# CuC_ControlComm.net
KiCad netlist of a schematic drawn in Altium Designer
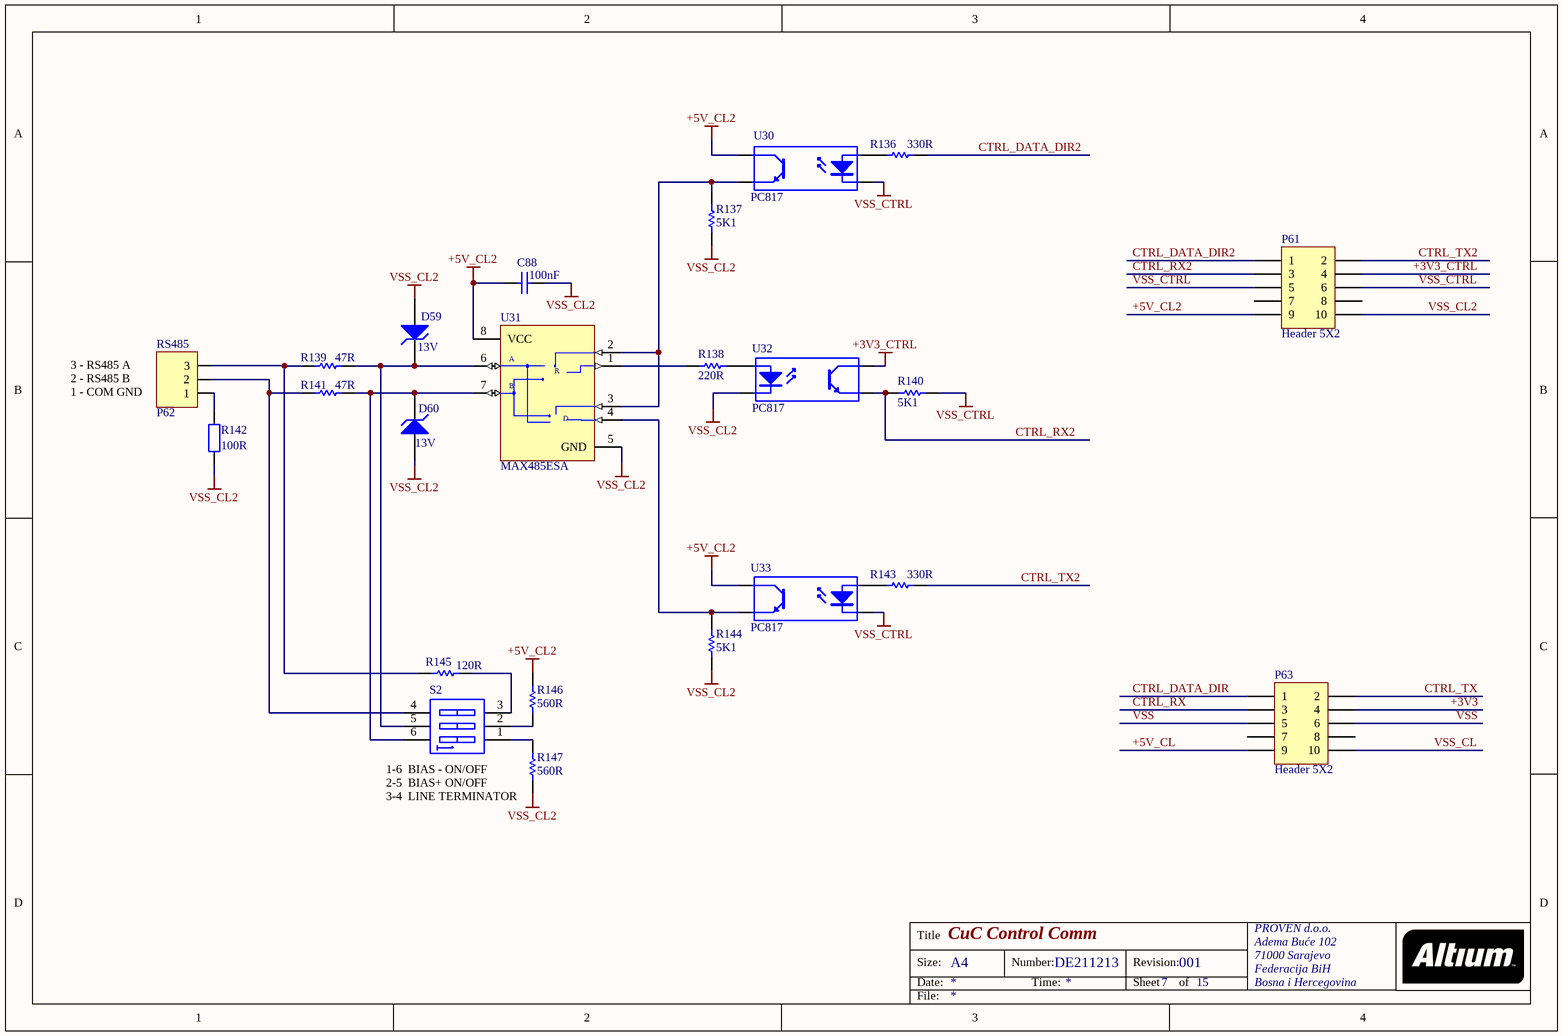
[diagram p0: CuC_ControlComm.SchDoc]

(export (version "E")
  (design (tool "Eeschema 10.0.6"))
  (components
    (comp (ref "C88")
      (value "100nF")
      (footprint "1206")
      (description "Ceramic Chip Capacitor - Standard")
      (fields (field (name "PUBLISHER") "Altium Limited"))
      (libsource (lib "KEMET Chip Capacitor") (part "C1206"))
    )
    (comp (ref "D59")
      (value "13V")
      (footprint "Miscellaneous Devices:DO-35A")
      (description "Zener Diode")
      (fields (field (name "PUBLISHER") "Altium Limited"))
      (libsource (lib "Miscellaneous Devices") (part "D Zener"))
    )
    (comp (ref "D60")
      (value "13V")
      (footprint "Miscellaneous Devices:DO-35A")
      (description "Zener Diode")
      (fields (field (name "PUBLISHER") "Altium Limited"))
      (libsource (lib "Miscellaneous Devices") (part "D Zener"))
    )
    (comp (ref "P61")
      (value "Header 5X2")
      (footprint "HDR2X5")
      (description "Header, 5-Pin, Dual row")
      (fields (field (name "PUBLISHER") "Altium Limited"))
      (libsource (lib "Miscellaneous Connectors") (part "Header 5X2"))
    )
    (comp (ref "P62")
      (value "RS485")
      (footprint "TERMINAL BLOK 3")
      (description "3 pinski terminal blok konektor")
      (libsource (lib "ProjectLibrary") (part "TERMINAL BLOK 3"))
    )
    (comp (ref "P63")
      (value "Header 5X2")
      (footprint "HDR2X5")
      (description "Header, 5-Pin, Dual row")
      (fields (field (name "PUBLISHER") "Altium Limited"))
      (libsource (lib "Miscellaneous Connectors") (part "Header 5X2"))
    )
    (comp (ref "R136")
      (value "330R")
      (footprint "ERA-0805")
      (fields (field (name "PUBLISHER") "Altium Limited"))
      (libsource (lib "Panasonic Resistor") (part "ERA6Y"))
    )
    (comp (ref "R137")
      (value "5K1")
      (footprint "8-1206")
      (description "Thick Film Chip Resistor, 1 Ohm to 10M Ohm Range, 5% Tolerance, 1206 Size, 0.25 W")
      (fields (field (name "PUBLISHER") "Altium Limited"))
      (libsource (lib "Panasonic Resistor") (part "ERJ8GE"))
    )
    (comp (ref "R138")
      (value "220R")
      (footprint "ERA-0805")
      (fields (field (name "PUBLISHER") "Altium Limited"))
      (libsource (lib "Panasonic Resistor") (part "ERAS"))
    )
    (comp (ref "R139")
      (value "47R")
      (footprint "ERA-0805")
      (fields (field (name "PUBLISHER") "Altium Limited"))
      (libsource (lib "Panasonic Resistor") (part "ERAS"))
    )
    (comp (ref "R140")
      (value "5K1")
      (footprint "8-1206")
      (description "Thick Film Chip Resistor, 1 Ohm to 10M Ohm Range, 5% Tolerance, 1206 Size, 0.25 W")
      (fields (field (name "PUBLISHER") "Altium Limited"))
      (libsource (lib "Panasonic Resistor") (part "ERJ8GE"))
    )
    (comp (ref "R141")
      (value "47R")
      (footprint "ERA-0805")
      (fields (field (name "PUBLISHER") "Altium Limited"))
      (libsource (lib "Panasonic Resistor") (part "ERAS"))
    )
    (comp (ref "R142")
      (value "100R")
      (footprint "AXIAL-0.4")
      (description "Resistor")
      (fields (field (name "PUBLISHER") "Altium Limited"))
      (libsource (lib "Miscellaneous Devices") (part "Res2"))
    )
    (comp (ref "R143")
      (value "330R")
      (footprint "ERA-0805")
      (fields (field (name "PUBLISHER") "Altium Limited"))
      (libsource (lib "Panasonic Resistor") (part "ERA6Y"))
    )
    (comp (ref "R144")
      (value "5K1")
      (footprint "8-1206")
      (description "Thick Film Chip Resistor, 1 Ohm to 10M Ohm Range, 5% Tolerance, 1206 Size, 0.25 W")
      (fields (field (name "PUBLISHER") "Altium Limited"))
      (libsource (lib "Panasonic Resistor") (part "ERJ8GE"))
    )
    (comp (ref "R145")
      (value "120R")
      (footprint "ERA-0805")
      (fields (field (name "PUBLISHER") "Altium Limited"))
      (libsource (lib "Panasonic Resistor") (part "ERAS"))
    )
    (comp (ref "R146")
      (value "560R")
      (footprint "ERA-0805")
      (fields (field (name "PUBLISHER") "Altium Limited"))
      (libsource (lib "Panasonic Resistor") (part "ERAS"))
    )
    (comp (ref "R147")
      (value "560R")
      (footprint "ERA-0805")
      (fields (field (name "PUBLISHER") "Altium Limited"))
      (libsource (lib "Panasonic Resistor") (part "ERAS"))
    )
    (comp (ref "S2")
      (value "~")
      (footprint "DIP-6")
      (description "DIP Switch, 3 Position, SPST")
      (fields (field (name "PUBLISHER") "Altium Limited"))
      (libsource (lib "Miscellaneous Devices") (part "SW DIP-3"))
    )
    (comp (ref "U30")
      (value "PC817")
      (footprint "DIP-4")
      (description "4-Pin Phototransistor Optocoupler")
      (fields (field (name "PUBLISHER") "Altium Limited"))
      (libsource (lib "Miscellaneous Devices") (part "Optoisolator1"))
    )
    (comp (ref "U31")
      (value "MAX485ESA")
      (footprint "NSO8_N")
      (description "Low-Power, Slew-Rate-Limited RS-485/RS-422 Transceiver")
      (fields (field (name "PUBLISHER") "Altium Limited"))
      (libsource (lib "Maxim Communication Transceiver") (part "MAX485ESA"))
    )
    (comp (ref "U32")
      (value "PC817")
      (footprint "DIP-4")
      (description "4-Pin Phototransistor Optocoupler")
      (fields (field (name "PUBLISHER") "Altium Limited"))
      (libsource (lib "Miscellaneous Devices") (part "Optoisolator1"))
    )
    (comp (ref "U33")
      (value "PC817")
      (footprint "DIP-4")
      (description "4-Pin Phototransistor Optocoupler")
      (fields (field (name "PUBLISHER") "Altium Limited"))
      (libsource (lib "Miscellaneous Devices") (part "Optoisolator1"))
    )
  )
  (nets
    (net (code "1") (name "+3V3_CTRL") (class "Default")
      (node (ref "P61") (pin "4") (pinfunction "4_4") (pintype "passive"))
      (node (ref "U32") (pin "4") (pinfunction "C_4") (pintype "passive"))
    )
    (net (code "2") (name "+5V_CL2") (class "Default")
      (node (ref "C88") (pin "2") (pinfunction "2_2") (pintype "passive"))
      (node (ref "P61") (pin "9") (pinfunction "9_9") (pintype "passive"))
      (node (ref "R146") (pin "2") (pinfunction "2_2") (pintype "passive"))
      (node (ref "U30") (pin "4") (pinfunction "C_4") (pintype "passive"))
      (node (ref "U31") (pin "8") (pinfunction "VCC_8") (pintype "power_in"))
      (node (ref "U33") (pin "4") (pinfunction "C_4") (pintype "passive"))
    )
    (net (code "3") (name "/+3V3") (class "Default")
      (node (ref "P63") (pin "4") (pinfunction "4_4") (pintype "passive"))
    )
    (net (code "4") (name "/+5V_CL") (class "Default")
      (node (ref "P63") (pin "9") (pinfunction "9_9") (pintype "passive"))
    )
    (net (code "5") (name "/CTRL_DATA_DIR") (class "Default")
      (node (ref "P63") (pin "1") (pinfunction "1_1") (pintype "passive"))
    )
    (net (code "6") (name "/CTRL_DATA_DIR2") (class "Default")
      (node (ref "P61") (pin "1") (pinfunction "1_1") (pintype "passive"))
      (node (ref "R136") (pin "2") (pinfunction "2_2") (pintype "passive"))
    )
    (net (code "7") (name "/CTRL_RX") (class "Default")
      (node (ref "P63") (pin "3") (pinfunction "3_3") (pintype "passive"))
    )
    (net (code "8") (name "/CTRL_RX2") (class "Default")
      (node (ref "P61") (pin "3") (pinfunction "3_3") (pintype "passive"))
      (node (ref "R140") (pin "1") (pinfunction "1_1") (pintype "passive"))
      (node (ref "U32") (pin "3") (pinfunction "E_3") (pintype "passive"))
    )
    (net (code "9") (name "/CTRL_TX") (class "Default")
      (node (ref "P63") (pin "2") (pinfunction "2_2") (pintype "passive"))
    )
    (net (code "10") (name "/CTRL_TX2") (class "Default")
      (node (ref "P61") (pin "2") (pinfunction "2_2") (pintype "passive"))
      (node (ref "R143") (pin "2") (pinfunction "2_2") (pintype "passive"))
    )
    (net (code "11") (name "/VSS") (class "Default")
      (node (ref "P63") (pin "5") (pinfunction "5_5") (pintype "passive"))
      (node (ref "P63") (pin "6") (pinfunction "6_6") (pintype "passive"))
    )
    (net (code "12") (name "/VSS_CL") (class "Default")
      (node (ref "P63") (pin "10") (pinfunction "10_10") (pintype "passive"))
    )
    (net (code "13") (name "Net-(D59-K)") (class "Default")
      (node (ref "D59") (pin "2") (pinfunction "K_2") (pintype "passive"))
      (node (ref "R139") (pin "2") (pinfunction "2_2") (pintype "passive"))
      (node (ref "S2") (pin "5") (pinfunction "B2_5") (pintype "passive"))
      (node (ref "U31") (pin "6") (pinfunction "A_6") (pintype "bidirectional"))
    )
    (net (code "14") (name "Net-(D60-K)") (class "Default")
      (node (ref "D60") (pin "2") (pinfunction "K_2") (pintype "passive"))
      (node (ref "R141") (pin "2") (pinfunction "2_2") (pintype "passive"))
      (node (ref "S2") (pin "6") (pinfunction "B1_6") (pintype "passive"))
      (node (ref "U31") (pin "7") (pinfunction "B_7") (pintype "bidirectional"))
    )
    (net (code "15") (name "Net-(P62-Pad1)") (class "Default")
      (node (ref "P62") (pin "1") (pinfunction "1_1") (pintype "passive"))
      (node (ref "R142") (pin "2") (pinfunction "2_2") (pintype "passive"))
    )
    (net (code "16") (name "Net-(P62-Pad3)") (class "Default")
      (node (ref "P62") (pin "3") (pinfunction "3_3") (pintype "passive"))
      (node (ref "R139") (pin "1") (pinfunction "1_1") (pintype "passive"))
      (node (ref "R145") (pin "1") (pinfunction "1_1") (pintype "passive"))
    )
    (net (code "17") (name "Net-(S2-A1)") (class "Default")
      (node (ref "R147") (pin "2") (pinfunction "2_2") (pintype "passive"))
      (node (ref "S2") (pin "1") (pinfunction "A1_1") (pintype "passive"))
    )
    (net (code "18") (name "Net-(S2-A2)") (class "Default")
      (node (ref "R146") (pin "1") (pinfunction "1_1") (pintype "passive"))
      (node (ref "S2") (pin "2") (pinfunction "A2_2") (pintype "passive"))
    )
    (net (code "19") (name "Net-(S2-A3)") (class "Default")
      (node (ref "R145") (pin "2") (pinfunction "2_2") (pintype "passive"))
      (node (ref "S2") (pin "3") (pinfunction "A3_3") (pintype "passive"))
    )
    (net (code "20") (name "Net-(S2-B3)") (class "Default")
      (node (ref "P62") (pin "2") (pinfunction "2_2") (pintype "passive"))
      (node (ref "R141") (pin "1") (pinfunction "1_1") (pintype "passive"))
      (node (ref "S2") (pin "4") (pinfunction "B3_4") (pintype "passive"))
    )
    (net (code "21") (name "Net-(U30-A)") (class "Default")
      (node (ref "R136") (pin "1") (pinfunction "1_1") (pintype "passive"))
      (node (ref "U30") (pin "1") (pinfunction "A_1") (pintype "passive"))
    )
    (net (code "22") (name "Net-(U30-E)") (class "Default")
      (node (ref "R137") (pin "2") (pinfunction "2_2") (pintype "passive"))
      (node (ref "U30") (pin "3") (pinfunction "E_3") (pintype "passive"))
      (node (ref "U31") (pin "2") (pinfunction "~{RE}_2") (pintype "input"))
      (node (ref "U31") (pin "3") (pinfunction "DE_3") (pintype "input"))
    )
    (net (code "23") (name "Net-(U31-DI)") (class "Default")
      (node (ref "R144") (pin "2") (pinfunction "2_2") (pintype "passive"))
      (node (ref "U31") (pin "4") (pinfunction "DI_4") (pintype "input"))
      (node (ref "U33") (pin "3") (pinfunction "E_3") (pintype "passive"))
    )
    (net (code "24") (name "Net-(U31-RO)") (class "Default")
      (node (ref "R138") (pin "2") (pinfunction "2_2") (pintype "passive"))
      (node (ref "U31") (pin "1") (pinfunction "RO_1") (pintype "output"))
    )
    (net (code "25") (name "Net-(U32-A)") (class "Default")
      (node (ref "R138") (pin "1") (pinfunction "1_1") (pintype "passive"))
      (node (ref "U32") (pin "1") (pinfunction "A_1") (pintype "passive"))
    )
    (net (code "26") (name "Net-(U33-A)") (class "Default")
      (node (ref "R143") (pin "1") (pinfunction "1_1") (pintype "passive"))
      (node (ref "U33") (pin "1") (pinfunction "A_1") (pintype "passive"))
    )
    (net (code "27") (name "VSS_CL2") (class "Default")
      (node (ref "C88") (pin "1") (pinfunction "1_1") (pintype "passive"))
      (node (ref "D59") (pin "1") (pinfunction "A_1") (pintype "passive"))
      (node (ref "D60") (pin "1") (pinfunction "A_1") (pintype "passive"))
      (node (ref "P61") (pin "10") (pinfunction "10_10") (pintype "passive"))
      (node (ref "R137") (pin "1") (pinfunction "1_1") (pintype "passive"))
      (node (ref "R142") (pin "1") (pinfunction "1_1") (pintype "passive"))
      (node (ref "R144") (pin "1") (pinfunction "1_1") (pintype "passive"))
      (node (ref "R147") (pin "1") (pinfunction "1_1") (pintype "passive"))
      (node (ref "U31") (pin "5") (pinfunction "GND_5") (pintype "power_in"))
      (node (ref "U32") (pin "2") (pinfunction "K_2") (pintype "passive"))
    )
    (net (code "28") (name "VSS_CTRL") (class "Default")
      (node (ref "P61") (pin "5") (pinfunction "5_5") (pintype "passive"))
      (node (ref "P61") (pin "6") (pinfunction "6_6") (pintype "passive"))
      (node (ref "R140") (pin "2") (pinfunction "2_2") (pintype "passive"))
      (node (ref "U30") (pin "2") (pinfunction "K_2") (pintype "passive"))
      (node (ref "U33") (pin "2") (pinfunction "K_2") (pintype "passive"))
    )
    (net (code "29") (name "unconnected-(P61-Pad7)") (class "Default")
      (node (ref "P61") (pin "7") (pinfunction "7_7") (pintype "passive"))
    )
    (net (code "30") (name "unconnected-(P61-Pad8)") (class "Default")
      (node (ref "P61") (pin "8") (pinfunction "8_8") (pintype "passive"))
    )
    (net (code "31") (name "unconnected-(P63-Pad7)") (class "Default")
      (node (ref "P63") (pin "7") (pinfunction "7_7") (pintype "passive"))
    )
    (net (code "32") (name "unconnected-(P63-Pad8)") (class "Default")
      (node (ref "P63") (pin "8") (pinfunction "8_8") (pintype "passive"))
    )
  )
)
